# LCD_LED.net
KiCad netlist of a schematic drawn in EAGLE
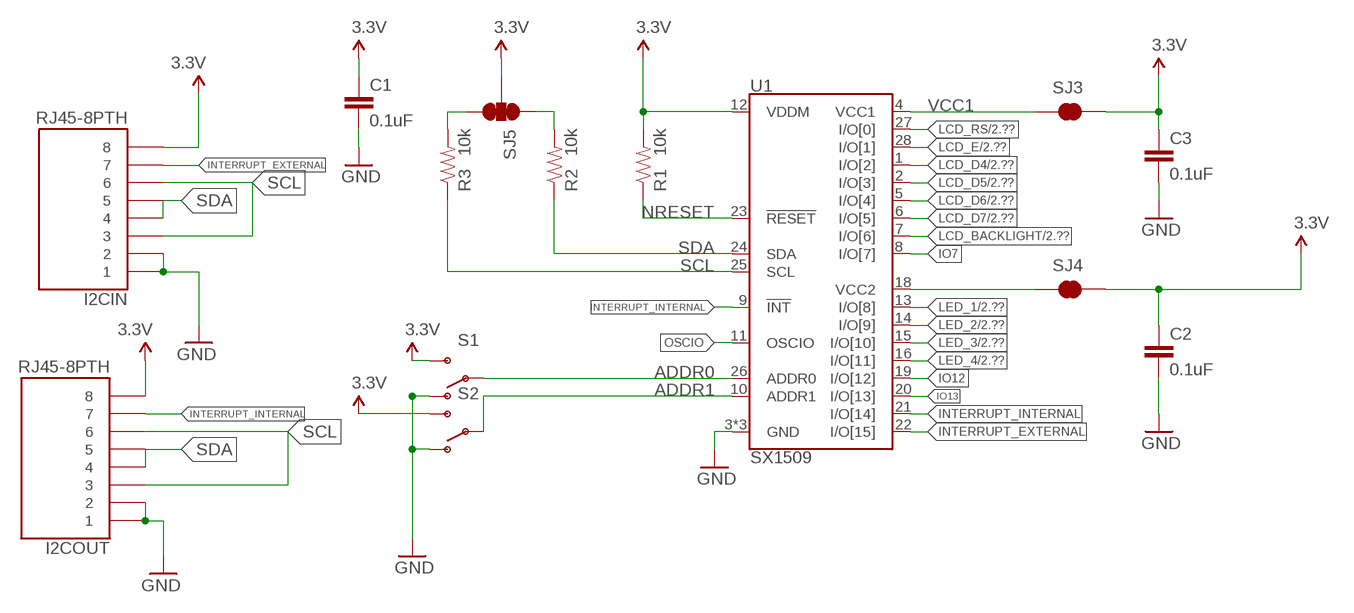
[diagram p0: schematic, sheet 1]
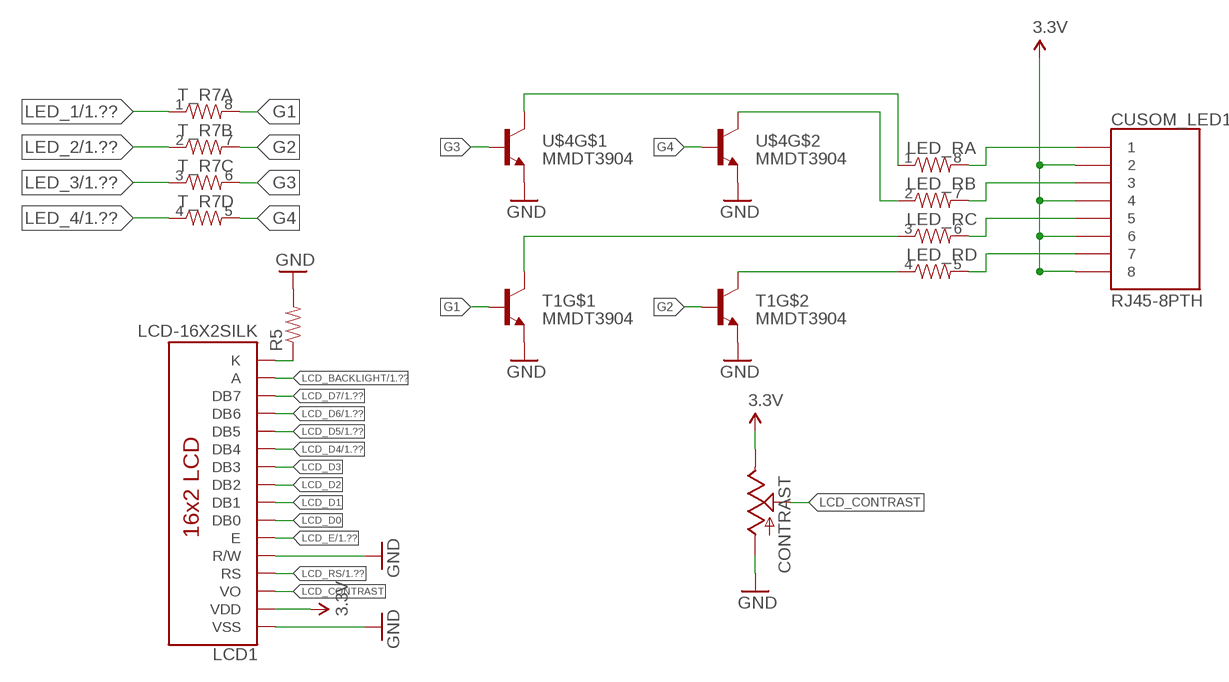
[diagram p1: schematic, sheet 2]

(export (version "E")
  (design (tool "Eeschema 10.0.6"))
  (components
    (comp (ref "CONTRAST")
      (value "POT")
      (footprint "eagle-import:ALPS_POT")
      (libsource (lib "eagle-import") (part "POT"))
    )
    (comp (ref "CUSOM_LED1")
      (value "RJ45-8PTH")
      (footprint "eagle-import:RJ45-8")
      (libsource (lib "eagle-import") (part "RJ45-8PTH"))
    )
    (comp (ref "LCD1")
      (value "LCD-16X2SILK")
      (footprint "eagle-import:LCD-16X2")
      (libsource (lib "eagle-import") (part "LCD-16X2SILK"))
    )
    (comp (ref "LED_R")
      (value "RESISTOR-ARRAY0603-ARV")
      (footprint "eagle-import:0603-ARV")
      (libsource (lib "eagle-import") (part "RESISTOR-ARRAY0603-ARV"))
    )
    (comp (ref "R5")
      (value "RESISTOR0603")
      (footprint "eagle-import:0603-RES")
      (libsource (lib "eagle-import") (part "RESISTOR0603"))
    )
    (comp (ref "T1")
      (value "MMDT3904")
      (footprint "eagle-import:SOT363")
      (libsource (lib "eagle-import") (part "MMDT3904"))
    )
    (comp (ref "T_R7")
      (value "RESISTOR-ARRAY0603-ARV")
      (footprint "eagle-import:0603-ARV")
      (libsource (lib "eagle-import") (part "RESISTOR-ARRAY0603-ARV"))
    )
    (comp (ref "U$4")
      (value "MMDT3904")
      (footprint "eagle-import:SOT363")
      (libsource (lib "eagle-import") (part "MMDT3904"))
    )
    (comp (ref "C1")
      (value "0.1uF")
      (footprint "eagle-import:0402-CAP")
      (libsource (lib "eagle-import") (part "CAP0402-CAP"))
    )
    (comp (ref "C2")
      (value "0.1uF")
      (footprint "eagle-import:0402-CAP")
      (libsource (lib "eagle-import") (part "CAP0402-CAP"))
    )
    (comp (ref "C3")
      (value "0.1uF")
      (footprint "eagle-import:0402-CAP")
      (libsource (lib "eagle-import") (part "CAP0402-CAP"))
    )
    (comp (ref "I2CIN")
      (value "RJ45-8PTH")
      (footprint "eagle-import:RJ45-8")
      (libsource (lib "eagle-import") (part "RJ45-8PTH"))
    )
    (comp (ref "I2COUT")
      (value "RJ45-8PTH")
      (footprint "eagle-import:RJ45-8")
      (libsource (lib "eagle-import") (part "RJ45-8PTH"))
    )
    (comp (ref "R1")
      (value "10k")
      (footprint "eagle-import:0402-RES")
      (libsource (lib "eagle-import") (part "RESISTOR0402-RES"))
    )
    (comp (ref "R2")
      (value "10k")
      (footprint "eagle-import:0402-RES")
      (libsource (lib "eagle-import") (part "RESISTOR0402-RES"))
    )
    (comp (ref "R3")
      (value "10k")
      (footprint "eagle-import:0402-RES")
      (libsource (lib "eagle-import") (part "RESISTOR0402-RES"))
    )
    (comp (ref "S1")
      (value "SWITCH-SPDT-SMD-A")
      (footprint "eagle-import:SWITCH-SPST-SMD-A")
      (libsource (lib "eagle-import") (part "SWITCH-SPDT-SMD-A"))
    )
    (comp (ref "S2")
      (value "SWITCH-SPDT-SMD-A")
      (footprint "eagle-import:SWITCH-SPST-SMD-A")
      (libsource (lib "eagle-import") (part "SWITCH-SPDT-SMD-A"))
    )
    (comp (ref "SJ3")
      (value "SOLDERJUMPERNO")
      (footprint "eagle-import:SJ_2S-NO")
      (libsource (lib "eagle-import") (part "SOLDERJUMPERNO"))
    )
    (comp (ref "SJ4")
      (value "SOLDERJUMPERNO")
      (footprint "eagle-import:SJ_2S-NO")
      (libsource (lib "eagle-import") (part "SOLDERJUMPERNO"))
    )
    (comp (ref "SJ5")
      (value "SOLDERJUMPER_2WAYS")
      (footprint "eagle-import:SJ_3")
      (libsource (lib "eagle-import") (part "SOLDERJUMPER_2WAYS"))
    )
    (comp (ref "U1")
      (value "SX1509")
      (footprint "eagle-import:QFN-28")
      (libsource (lib "eagle-import") (part "SX1509"))
    )
  )
  (nets
    (net (code "1") (name "3.3V") (class "Default")
      (node (ref "C1") (pin "1") (pinfunction "1_1") (pintype "passive"))
      (node (ref "C2") (pin "1") (pinfunction "1_1") (pintype "passive"))
      (node (ref "C3") (pin "1") (pinfunction "1_1") (pintype "passive"))
      (node (ref "CONTRAST") (pin "P$1") (pinfunction "E_P$1") (pintype "passive"))
      (node (ref "CUSOM_LED1") (pin "2") (pinfunction "2_2") (pintype "bidirectional"))
      (node (ref "CUSOM_LED1") (pin "4") (pinfunction "4_4") (pintype "bidirectional"))
      (node (ref "CUSOM_LED1") (pin "6") (pinfunction "6_6") (pintype "bidirectional"))
      (node (ref "CUSOM_LED1") (pin "8") (pinfunction "8_8") (pintype "bidirectional"))
      (node (ref "I2CIN") (pin "8") (pinfunction "8_8") (pintype "bidirectional"))
      (node (ref "I2COUT") (pin "8") (pinfunction "8_8") (pintype "bidirectional"))
      (node (ref "LCD1") (pin "2") (pinfunction "VDD_2") (pintype "power_in"))
      (node (ref "R1") (pin "2") (pinfunction "2_2") (pintype "passive"))
      (node (ref "S1") (pin "3") (pinfunction "S_3") (pintype "passive"))
      (node (ref "S2") (pin "3") (pinfunction "S_3") (pintype "passive"))
      (node (ref "SJ3") (pin "2") (pinfunction "2_2") (pintype "passive"))
      (node (ref "SJ4") (pin "2") (pinfunction "2_2") (pintype "passive"))
      (node (ref "SJ5") (pin "2") (pinfunction "2_2") (pintype "passive"))
      (node (ref "U1") (pin "12") (pinfunction "VDDM_12") (pintype "bidirectional"))
    )
    (net (code "2") (name "ADDR0") (class "Default")
      (node (ref "S1") (pin "2") (pinfunction "P_2") (pintype "passive"))
      (node (ref "U1") (pin "26") (pinfunction "ADDR0_26") (pintype "bidirectional"))
    )
    (net (code "3") (name "ADDR1") (class "Default")
      (node (ref "S2") (pin "2") (pinfunction "P_2") (pintype "passive"))
      (node (ref "U1") (pin "10") (pinfunction "ADDR1_10") (pintype "bidirectional"))
    )
    (net (code "4") (name "G1") (class "Default")
      (node (ref "T1") (pin "5") (pinfunction "B_5") (pintype "passive"))
      (node (ref "T_R7") (pin "8") (pinfunction "2_8") (pintype "passive"))
    )
    (net (code "5") (name "G2") (class "Default")
      (node (ref "T1") (pin "2") (pinfunction "B_2") (pintype "passive"))
      (node (ref "T_R7") (pin "7") (pinfunction "2_7") (pintype "passive"))
    )
    (net (code "6") (name "G3") (class "Default")
      (node (ref "T_R7") (pin "6") (pinfunction "2_6") (pintype "passive"))
      (node (ref "U$4") (pin "5") (pinfunction "B_5") (pintype "passive"))
    )
    (net (code "7") (name "G4") (class "Default")
      (node (ref "T_R7") (pin "5") (pinfunction "2_5") (pintype "passive"))
      (node (ref "U$4") (pin "2") (pinfunction "B_2") (pintype "passive"))
    )
    (net (code "8") (name "GND") (class "Default")
      (node (ref "C1") (pin "2") (pinfunction "2_2") (pintype "passive"))
      (node (ref "C2") (pin "2") (pinfunction "2_2") (pintype "passive"))
      (node (ref "C3") (pin "2") (pinfunction "2_2") (pintype "passive"))
      (node (ref "CONTRAST") (pin "P$3") (pinfunction "A_P$3") (pintype "passive"))
      (node (ref "I2CIN") (pin "1") (pinfunction "1_1") (pintype "bidirectional"))
      (node (ref "I2CIN") (pin "2") (pinfunction "2_2") (pintype "bidirectional"))
      (node (ref "I2COUT") (pin "1") (pinfunction "1_1") (pintype "bidirectional"))
      (node (ref "I2COUT") (pin "2") (pinfunction "2_2") (pintype "bidirectional"))
      (node (ref "LCD1") (pin "1") (pinfunction "VSS_1") (pintype "power_in"))
      (node (ref "LCD1") (pin "5") (pinfunction "R/W_5") (pintype "input"))
      (node (ref "R5") (pin "2") (pinfunction "2_2") (pintype "passive"))
      (node (ref "S1") (pin "1") (pinfunction "O_1") (pintype "passive"))
      (node (ref "S2") (pin "1") (pinfunction "O_1") (pintype "passive"))
      (node (ref "T1") (pin "1") (pinfunction "E_1") (pintype "passive"))
      (node (ref "T1") (pin "4") (pinfunction "E_4") (pintype "passive"))
      (node (ref "U$4") (pin "1") (pinfunction "E_1") (pintype "passive"))
      (node (ref "U$4") (pin "4") (pinfunction "E_4") (pintype "passive"))
      (node (ref "U1") (pin "17") (pinfunction "GND_17") (pintype "bidirectional"))
      (node (ref "U1") (pin "29") (pinfunction "GND_29") (pintype "bidirectional"))
      (node (ref "U1") (pin "3") (pinfunction "GND_3") (pintype "bidirectional"))
    )
    (net (code "9") (name "INTERRUPT_EXTERNAL") (class "Default")
      (node (ref "I2CIN") (pin "7") (pinfunction "7_7") (pintype "bidirectional"))
      (node (ref "U1") (pin "22") (pinfunction "I/O[15]_22") (pintype "bidirectional"))
    )
    (net (code "10") (name "INTERRUPT_INTERNAL") (class "Default")
      (node (ref "I2COUT") (pin "7") (pinfunction "7_7") (pintype "bidirectional"))
      (node (ref "U1") (pin "21") (pinfunction "I/O[14]_21") (pintype "bidirectional"))
      (node (ref "U1") (pin "9") (pinfunction "~{INT}_9") (pintype "bidirectional"))
    )
    (net (code "11") (name "IO7") (class "Default")
      (node (ref "U1") (pin "8") (pinfunction "I/O[7]_8") (pintype "bidirectional"))
    )
    (net (code "12") (name "IO12") (class "Default")
      (node (ref "U1") (pin "19") (pinfunction "I/O[12]_19") (pintype "bidirectional"))
    )
    (net (code "13") (name "IO13") (class "Default")
      (node (ref "U1") (pin "20") (pinfunction "I/O[13]_20") (pintype "bidirectional"))
    )
    (net (code "14") (name "LCD_BACKLIGHT") (class "Default")
      (node (ref "LCD1") (pin "15") (pinfunction "A_15") (pintype "power_in"))
      (node (ref "U1") (pin "7") (pinfunction "I/O[6]_7") (pintype "bidirectional"))
    )
    (net (code "15") (name "LCD_CONTRAST") (class "Default")
      (node (ref "CONTRAST") (pin "P$2") (pinfunction "S_P$2") (pintype "passive"))
      (node (ref "LCD1") (pin "3") (pinfunction "VO_3") (pintype "bidirectional"))
    )
    (net (code "16") (name "LCD_D0") (class "Default")
      (node (ref "LCD1") (pin "7") (pinfunction "DB0_7") (pintype "bidirectional"))
    )
    (net (code "17") (name "LCD_D1") (class "Default")
      (node (ref "LCD1") (pin "8") (pinfunction "DB1_8") (pintype "bidirectional"))
    )
    (net (code "18") (name "LCD_D2") (class "Default")
      (node (ref "LCD1") (pin "9") (pinfunction "DB2_9") (pintype "bidirectional"))
    )
    (net (code "19") (name "LCD_D3") (class "Default")
      (node (ref "LCD1") (pin "10") (pinfunction "DB3_10") (pintype "bidirectional"))
    )
    (net (code "20") (name "LCD_D4") (class "Default")
      (node (ref "LCD1") (pin "11") (pinfunction "DB4_11") (pintype "bidirectional"))
      (node (ref "U1") (pin "1") (pinfunction "I/O[2]_1") (pintype "bidirectional"))
    )
    (net (code "21") (name "LCD_D5") (class "Default")
      (node (ref "LCD1") (pin "12") (pinfunction "DB5_12") (pintype "bidirectional"))
      (node (ref "U1") (pin "2") (pinfunction "I/O[3]_2") (pintype "bidirectional"))
    )
    (net (code "22") (name "LCD_D6") (class "Default")
      (node (ref "LCD1") (pin "13") (pinfunction "DB6_13") (pintype "bidirectional"))
      (node (ref "U1") (pin "5") (pinfunction "I/O[4]_5") (pintype "bidirectional"))
    )
    (net (code "23") (name "LCD_D7") (class "Default")
      (node (ref "LCD1") (pin "14") (pinfunction "DB7_14") (pintype "bidirectional"))
      (node (ref "U1") (pin "6") (pinfunction "I/O[5]_6") (pintype "bidirectional"))
    )
    (net (code "24") (name "LCD_E") (class "Default")
      (node (ref "LCD1") (pin "6") (pinfunction "E_6") (pintype "input"))
      (node (ref "U1") (pin "28") (pinfunction "I/O[1]_28") (pintype "bidirectional"))
    )
    (net (code "25") (name "LCD_RS") (class "Default")
      (node (ref "LCD1") (pin "4") (pinfunction "RS_4") (pintype "input"))
      (node (ref "U1") (pin "27") (pinfunction "I/O[0]_27") (pintype "bidirectional"))
    )
    (net (code "26") (name "LED_1") (class "Default")
      (node (ref "T_R7") (pin "1") (pinfunction "1_1") (pintype "passive"))
      (node (ref "U1") (pin "13") (pinfunction "I/O[8]_13") (pintype "bidirectional"))
    )
    (net (code "27") (name "LED_2") (class "Default")
      (node (ref "T_R7") (pin "2") (pinfunction "1_2") (pintype "passive"))
      (node (ref "U1") (pin "14") (pinfunction "I/O[9]_14") (pintype "bidirectional"))
    )
    (net (code "28") (name "LED_3") (class "Default")
      (node (ref "T_R7") (pin "3") (pinfunction "1_3") (pintype "passive"))
      (node (ref "U1") (pin "15") (pinfunction "I/O[10]_15") (pintype "bidirectional"))
    )
    (net (code "29") (name "LED_4") (class "Default")
      (node (ref "T_R7") (pin "4") (pinfunction "1_4") (pintype "passive"))
      (node (ref "U1") (pin "16") (pinfunction "I/O[11]_16") (pintype "bidirectional"))
    )
    (net (code "30") (name "NRESET") (class "Default")
      (node (ref "R1") (pin "1") (pinfunction "1_1") (pintype "passive"))
      (node (ref "U1") (pin "23") (pinfunction "~{RESET}_23") (pintype "bidirectional"))
    )
    (net (code "31") (name "Net-(LCD1-K)") (class "Default")
      (node (ref "LCD1") (pin "16") (pinfunction "K_16") (pintype "power_in"))
      (node (ref "R5") (pin "1") (pinfunction "1_1") (pintype "passive"))
    )
    (net (code "32") (name "Net-(LED_RA-2)") (class "Default")
      (node (ref "CUSOM_LED1") (pin "1") (pinfunction "1_1") (pintype "bidirectional"))
      (node (ref "LED_R") (pin "8") (pinfunction "2_8") (pintype "passive"))
    )
    (net (code "33") (name "Net-(LED_RB-1)") (class "Default")
      (node (ref "LED_R") (pin "2") (pinfunction "1_2") (pintype "passive"))
      (node (ref "U$4") (pin "6") (pinfunction "C_6") (pintype "passive"))
    )
    (net (code "34") (name "Net-(LED_RB-2)") (class "Default")
      (node (ref "CUSOM_LED1") (pin "3") (pinfunction "3_3") (pintype "bidirectional"))
      (node (ref "LED_R") (pin "7") (pinfunction "2_7") (pintype "passive"))
    )
    (net (code "35") (name "Net-(LED_RC-1)") (class "Default")
      (node (ref "LED_R") (pin "3") (pinfunction "1_3") (pintype "passive"))
      (node (ref "T1") (pin "3") (pinfunction "C_3") (pintype "passive"))
    )
    (net (code "36") (name "Net-(LED_RC-2)") (class "Default")
      (node (ref "CUSOM_LED1") (pin "5") (pinfunction "5_5") (pintype "bidirectional"))
      (node (ref "LED_R") (pin "6") (pinfunction "2_6") (pintype "passive"))
    )
    (net (code "37") (name "Net-(LED_RD-1)") (class "Default")
      (node (ref "LED_R") (pin "4") (pinfunction "1_4") (pintype "passive"))
      (node (ref "T1") (pin "6") (pinfunction "C_6") (pintype "passive"))
    )
    (net (code "38") (name "Net-(LED_RD-2)") (class "Default")
      (node (ref "CUSOM_LED1") (pin "7") (pinfunction "7_7") (pintype "bidirectional"))
      (node (ref "LED_R") (pin "5") (pinfunction "2_5") (pintype "passive"))
    )
    (net (code "39") (name "Net-(R2-Pad2)") (class "Default")
      (node (ref "R2") (pin "2") (pinfunction "2_2") (pintype "passive"))
      (node (ref "SJ5") (pin "1") (pinfunction "1_1") (pintype "passive"))
    )
    (net (code "40") (name "Net-(R3-Pad2)") (class "Default")
      (node (ref "R3") (pin "2") (pinfunction "2_2") (pintype "passive"))
      (node (ref "SJ5") (pin "3") (pinfunction "3_3") (pintype "passive"))
    )
    (net (code "41") (name "Net-(U$4A-C)") (class "Default")
      (node (ref "LED_R") (pin "1") (pinfunction "1_1") (pintype "passive"))
      (node (ref "U$4") (pin "3") (pinfunction "C_3") (pintype "passive"))
    )
    (net (code "42") (name "Net-(U1-VCC2)") (class "Default")
      (node (ref "SJ4") (pin "1") (pinfunction "1_1") (pintype "passive"))
      (node (ref "U1") (pin "18") (pinfunction "VCC2_18") (pintype "bidirectional"))
    )
    (net (code "43") (name "OSCIO") (class "Default")
      (node (ref "U1") (pin "11") (pinfunction "OSCIO_11") (pintype "bidirectional"))
    )
    (net (code "44") (name "SCL") (class "Default")
      (node (ref "I2CIN") (pin "3") (pinfunction "3_3") (pintype "bidirectional"))
      (node (ref "I2CIN") (pin "6") (pinfunction "6_6") (pintype "bidirectional"))
      (node (ref "I2COUT") (pin "3") (pinfunction "3_3") (pintype "bidirectional"))
      (node (ref "I2COUT") (pin "6") (pinfunction "6_6") (pintype "bidirectional"))
      (node (ref "R3") (pin "1") (pinfunction "1_1") (pintype "passive"))
      (node (ref "U1") (pin "25") (pinfunction "SCL_25") (pintype "bidirectional"))
    )
    (net (code "45") (name "SDA") (class "Default")
      (node (ref "I2CIN") (pin "4") (pinfunction "4_4") (pintype "bidirectional"))
      (node (ref "I2CIN") (pin "5") (pinfunction "5_5") (pintype "bidirectional"))
      (node (ref "I2COUT") (pin "4") (pinfunction "4_4") (pintype "bidirectional"))
      (node (ref "I2COUT") (pin "5") (pinfunction "5_5") (pintype "bidirectional"))
      (node (ref "R2") (pin "1") (pinfunction "1_1") (pintype "passive"))
      (node (ref "U1") (pin "24") (pinfunction "SDA_24") (pintype "bidirectional"))
    )
    (net (code "46") (name "VCC1") (class "Default")
      (node (ref "SJ3") (pin "1") (pinfunction "1_1") (pintype "passive"))
      (node (ref "U1") (pin "4") (pinfunction "VCC1_4") (pintype "bidirectional"))
    )
  )
)
